# Arduino-MEGA.net
KiCad netlist of a schematic drawn in EAGLE
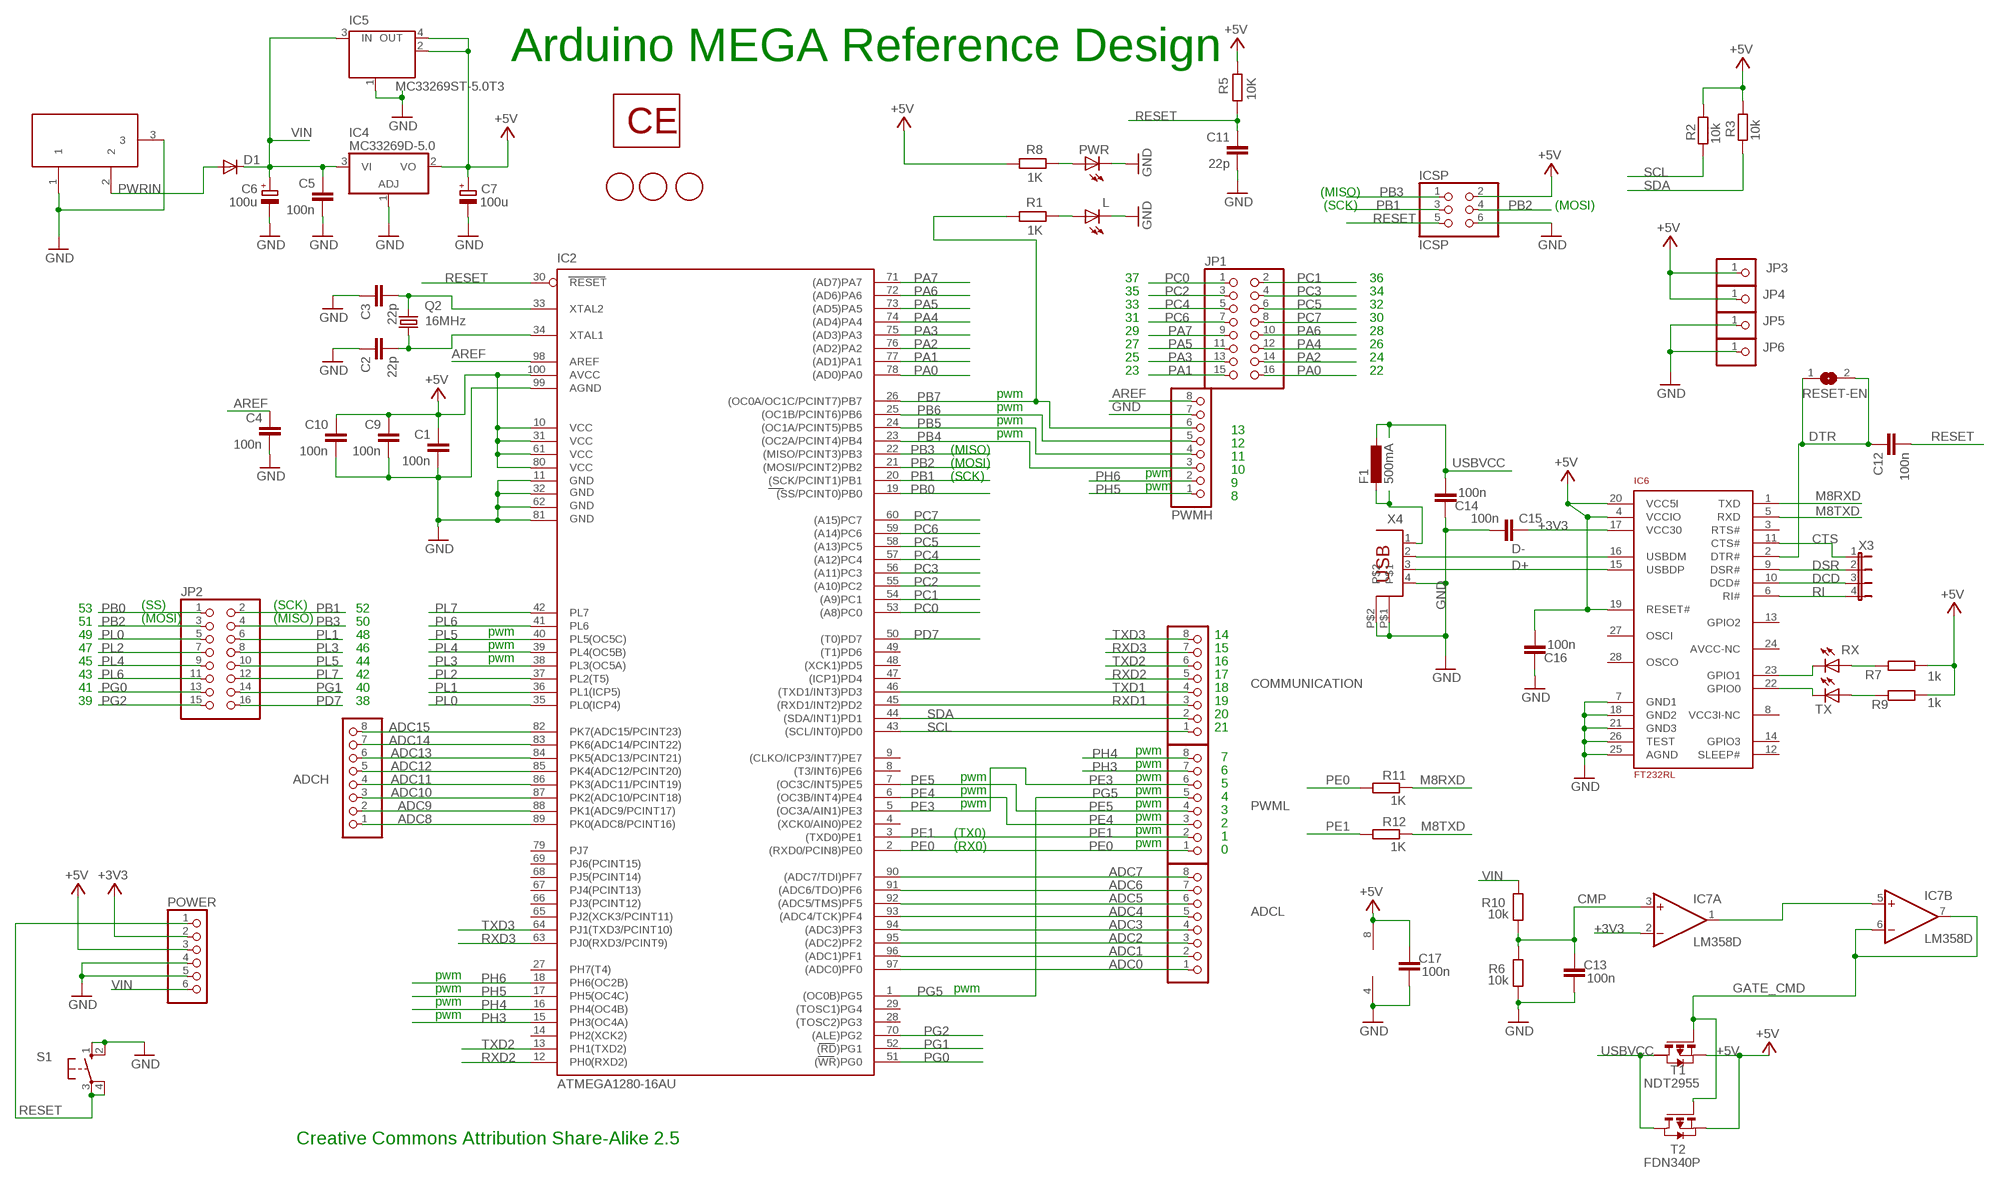
[diagram p0: schematic, sheet 1]

(export (version "E")
  (design (tool "Eeschema 10.0.6"))
  (components
    (comp (ref "ADCH")
      (value "PINHD-1X8")
      (footprint "eagle-import:1X08")
      (libsource (lib "eagle-import") (part "PINHD-1X8"))
    )
    (comp (ref "ADCL")
      (value "PINHD-1X8")
      (footprint "eagle-import:1X08")
      (libsource (lib "eagle-import") (part "PINHD-1X8"))
    )
    (comp (ref "C1")
      (value "100n")
      (footprint "eagle-import:C0805RND")
      (libsource (lib "eagle-import") (part "C-EU"))
    )
    (comp (ref "C2")
      (value "22p")
      (footprint "eagle-import:C0805RND")
      (libsource (lib "eagle-import") (part "C-EU"))
    )
    (comp (ref "C3")
      (value "22p")
      (footprint "eagle-import:C0805RND")
      (libsource (lib "eagle-import") (part "C-EU"))
    )
    (comp (ref "C4")
      (value "100n")
      (footprint "eagle-import:C0805RND")
      (libsource (lib "eagle-import") (part "C-EU"))
    )
    (comp (ref "C5")
      (value "100n")
      (footprint "eagle-import:C0805RND")
      (libsource (lib "eagle-import") (part "C-EU"))
    )
    (comp (ref "C6")
      (value "100u")
      (footprint "eagle-import:SMC_D")
      (libsource (lib "eagle-import") (part "CPOL-EUSMCD"))
    )
    (comp (ref "C7")
      (value "100u")
      (footprint "eagle-import:SMC_D")
      (libsource (lib "eagle-import") (part "CPOL-EUSMCD"))
    )
    (comp (ref "C9")
      (value "100n")
      (footprint "eagle-import:C0805RND")
      (libsource (lib "eagle-import") (part "C-EU"))
    )
    (comp (ref "C10")
      (value "100n")
      (footprint "eagle-import:C0805RND")
      (libsource (lib "eagle-import") (part "C-EU"))
    )
    (comp (ref "C11")
      (value "22p")
      (footprint "eagle-import:C0805RND")
      (libsource (lib "eagle-import") (part "C-EU"))
    )
    (comp (ref "C12")
      (value "100n")
      (footprint "eagle-import:C0805RND")
      (libsource (lib "eagle-import") (part "C-EU"))
    )
    (comp (ref "C13")
      (value "100n")
      (footprint "eagle-import:C0805RND")
      (libsource (lib "eagle-import") (part "C-EU"))
    )
    (comp (ref "C14")
      (value "100n")
      (footprint "eagle-import:C0805RND")
      (libsource (lib "eagle-import") (part "C-EU"))
    )
    (comp (ref "C15")
      (value "100n")
      (footprint "eagle-import:C0805RND")
      (libsource (lib "eagle-import") (part "C-EU"))
    )
    (comp (ref "C16")
      (value "100n")
      (footprint "eagle-import:C0805RND")
      (libsource (lib "eagle-import") (part "C-EU"))
    )
    (comp (ref "C17")
      (value "100n")
      (footprint "eagle-import:C0805RND")
      (libsource (lib "eagle-import") (part "C-EU"))
    )
    (comp (ref "COMMUNICATION")
      (value "PINHD-1X8")
      (footprint "eagle-import:1X08")
      (libsource (lib "eagle-import") (part "PINHD-1X8"))
    )
    (comp (ref "D1")
      (value "DIODE-SMB")
      (footprint "eagle-import:SMB")
      (libsource (lib "eagle-import") (part "DIODE-SMB"))
    )
    (comp (ref "F1")
      (value "500mA")
      (footprint "eagle-import:L1812")
      (libsource (lib "eagle-import") (part "L-EUL1812"))
    )
    (comp (ref "IC2")
      (value "ATMEGA1280-16AU")
      (footprint "eagle-import:TQFP100")
      (libsource (lib "eagle-import") (part "ATMEGAAU1280-16"))
    )
    (comp (ref "IC4")
      (value "MC33269D-5.0")
      (footprint "eagle-import:DPACK")
      (libsource (lib "eagle-import") (part "MC33269?D-5.0"))
    )
    (comp (ref "IC5")
      (value "MC33269ST-5.0T3")
      (footprint "eagle-import:SOT223")
      (libsource (lib "eagle-import") (part "MC33269ST-3.3T3"))
    )
    (comp (ref "IC6")
      (value "FT232RL")
      (footprint "eagle-import:SSOP28")
      (libsource (lib "eagle-import") (part "FT232RL"))
    )
    (comp (ref "IC7")
      (value "LM358D")
      (footprint "eagle-import:SO08")
      (libsource (lib "eagle-import") (part "LM358D"))
    )
    (comp (ref "ICSP")
      (value "ICSP")
      (footprint "eagle-import:2X03")
      (libsource (lib "eagle-import") (part "PINHD-2X3"))
    )
    (comp (ref "JP1")
      (value "PINHD-2X8")
      (footprint "eagle-import:2X08")
      (libsource (lib "eagle-import") (part "PINHD-2X8"))
    )
    (comp (ref "JP2")
      (value "PINHD-2X8")
      (footprint "eagle-import:2X08")
      (libsource (lib "eagle-import") (part "PINHD-2X8"))
    )
    (comp (ref "JP3")
      (value "PINHD-1X1")
      (footprint "eagle-import:1X01")
      (libsource (lib "eagle-import") (part "PINHD-1X1"))
    )
    (comp (ref "JP4")
      (value "PINHD-1X1")
      (footprint "eagle-import:1X01")
      (libsource (lib "eagle-import") (part "PINHD-1X1"))
    )
    (comp (ref "JP5")
      (value "PINHD-1X1")
      (footprint "eagle-import:1X01")
      (libsource (lib "eagle-import") (part "PINHD-1X1"))
    )
    (comp (ref "JP6")
      (value "PINHD-1X1")
      (footprint "eagle-import:1X01")
      (libsource (lib "eagle-import") (part "PINHD-1X1"))
    )
    (comp (ref "L")
      (value "LED0805ROUND")
      (footprint "eagle-import:0805RND")
      (libsource (lib "eagle-import") (part "LED0805ROUND"))
    )
    (comp (ref "POWER")
      (value "PINHD-1X6")
      (footprint "eagle-import:1X06")
      (libsource (lib "eagle-import") (part "PINHD-1X6"))
    )
    (comp (ref "PWMH")
      (value "PINHD-1X8")
      (footprint "eagle-import:1X08")
      (libsource (lib "eagle-import") (part "PINHD-1X8"))
    )
    (comp (ref "PWML")
      (value "PINHD-1X8")
      (footprint "eagle-import:1X08")
      (libsource (lib "eagle-import") (part "PINHD-1X8"))
    )
    (comp (ref "PWR")
      (value "LED0805ROUND")
      (footprint "eagle-import:0805RND")
      (libsource (lib "eagle-import") (part "LED0805ROUND"))
    )
    (comp (ref "Q2")
      (value "16MHz")
      (footprint "eagle-import:HC49_S")
      (libsource (lib "eagle-import") (part "CRYTALHC49S"))
    )
    (comp (ref "R1")
      (value "1K")
      (footprint "eagle-import:R0805RND")
      (libsource (lib "eagle-import") (part "rcl_R-EU_"))
    )
    (comp (ref "R2")
      (value "10k")
      (footprint "eagle-import:R0805RND")
      (libsource (lib "eagle-import") (part "rcl_R-EU_"))
    )
    (comp (ref "R3")
      (value "10k")
      (footprint "eagle-import:R0805RND")
      (libsource (lib "eagle-import") (part "rcl_R-EU_"))
    )
    (comp (ref "R5")
      (value "10K")
      (footprint "eagle-import:R0805RND")
      (libsource (lib "eagle-import") (part "rcl_R-EU_"))
    )
    (comp (ref "R6")
      (value "10k")
      (footprint "eagle-import:R0805RND")
      (libsource (lib "eagle-import") (part "rcl_R-EU_"))
    )
    (comp (ref "R7")
      (value "1k")
      (footprint "eagle-import:R0805RND")
      (libsource (lib "eagle-import") (part "rcl_R-EU_"))
    )
    (comp (ref "R8")
      (value "1K")
      (footprint "eagle-import:R0805RND")
      (libsource (lib "eagle-import") (part "rcl_R-EU_"))
    )
    (comp (ref "R9")
      (value "1k")
      (footprint "eagle-import:R0805RND")
      (libsource (lib "eagle-import") (part "rcl_R-EU_"))
    )
    (comp (ref "R10")
      (value "10k")
      (footprint "eagle-import:R0805RND")
      (libsource (lib "eagle-import") (part "rcl_R-EU_"))
    )
    (comp (ref "R11")
      (value "1K")
      (footprint "eagle-import:RCL_0805RND")
      (libsource (lib "eagle-import") (part "R-EU_"))
    )
    (comp (ref "R12")
      (value "1K")
      (footprint "eagle-import:RCL_0805RND")
      (libsource (lib "eagle-import") (part "R-EU_"))
    )
    (comp (ref "RESET-EN")
      (value "SJ")
      (footprint "eagle-import:SJ")
      (libsource (lib "eagle-import") (part "SJ"))
    )
    (comp (ref "RX")
      (value "LED0805ROUND")
      (footprint "eagle-import:0805RND")
      (libsource (lib "eagle-import") (part "LED0805ROUND"))
    )
    (comp (ref "S1")
      (value "10-XX")
      (footprint "eagle-import:B3F-10XX")
      (libsource (lib "eagle-import") (part "10-XX"))
    )
    (comp (ref "T1")
      (value "NDT2955")
      (footprint "eagle-import:SOT223")
      (libsource (lib "eagle-import") (part "PMOSSOT223"))
    )
    (comp (ref "T2")
      (value "FDN340P")
      (footprint "eagle-import:SOT-23")
      (libsource (lib "eagle-import") (part "PMOSSOT23"))
    )
    (comp (ref "TX")
      (value "LED0805ROUND")
      (footprint "eagle-import:0805RND")
      (libsource (lib "eagle-import") (part "LED0805ROUND"))
    )
    (comp (ref "U$1")
      (value "FIDUCIALMOUNT")
      (footprint "eagle-import:FIDUCIA-MOUNT")
      (libsource (lib "eagle-import") (part "FIDUCIALMOUNT"))
    )
    (comp (ref "U$2")
      (value "FIDUCIALMOUNT")
      (footprint "eagle-import:FIDUCIA-MOUNT")
      (libsource (lib "eagle-import") (part "FIDUCIALMOUNT"))
    )
    (comp (ref "U$3")
      (value "FIDUCIALMOUNT")
      (footprint "eagle-import:FIDUCIA-MOUNT")
      (libsource (lib "eagle-import") (part "FIDUCIALMOUNT"))
    )
    (comp (ref "U$4")
      (value "CE")
      (footprint "eagle-import:CE-COPPER")
      (libsource (lib "eagle-import") (part "CE"))
    )
    (comp (ref "X2")
      (value "DC21MMX")
      (footprint "eagle-import:DC-21MM")
      (libsource (lib "eagle-import") (part "DC21MMX"))
    )
    (comp (ref "X3")
      (value "JP4E")
      (footprint "eagle-import:JP4")
      (libsource (lib "eagle-import") (part "JP4E"))
    )
    (comp (ref "X4")
      (value "PN61729")
      (footprint "eagle-import:PN61729")
      (libsource (lib "eagle-import") (part "PN61729"))
    )
  )
  (nets
    (net (code "1") (name "+3V3") (class "Default")
      (node (ref "C15") (pin "2") (pinfunction "2_2") (pintype "passive"))
      (node (ref "IC6") (pin "17") (pinfunction "VCC30_17") (pintype "power_in"))
      (node (ref "IC7") (pin "2") (pinfunction "-IN_2") (pintype "input"))
      (node (ref "POWER") (pin "2") (pinfunction "2_2") (pintype "passive"))
    )
    (net (code "2") (name "+5V") (class "Default")
      (node (ref "C1") (pin "1") (pinfunction "1_1") (pintype "passive"))
      (node (ref "C10") (pin "1") (pinfunction "1_1") (pintype "passive"))
      (node (ref "C16") (pin "1") (pinfunction "1_1") (pintype "passive"))
      (node (ref "C17") (pin "2") (pinfunction "2_2") (pintype "passive"))
      (node (ref "C7") (pin "+") (pinfunction "+_+") (pintype "passive"))
      (node (ref "C9") (pin "1") (pinfunction "1_1") (pintype "passive"))
      (node (ref "IC2") (pin "10") (pinfunction "VCC_10") (pintype "power_in"))
      (node (ref "IC2") (pin "100") (pinfunction "AVCC_100") (pintype "power_in"))
      (node (ref "IC2") (pin "31") (pinfunction "VCC1_31") (pintype "power_in"))
      (node (ref "IC2") (pin "61") (pinfunction "VCC2_61") (pintype "power_in"))
      (node (ref "IC2") (pin "80") (pinfunction "VCC3_80") (pintype "power_in"))
      (node (ref "IC4") (pin "2") (pinfunction "VO_2") (pintype "passive"))
      (node (ref "IC5") (pin "2") (pinfunction "OUT_2") (pintype "passive"))
      (node (ref "IC5") (pin "4") (pinfunction "OUT_4") (pintype "passive"))
      (node (ref "IC6") (pin "19") (pinfunction "RESET#_19") (pintype "input"))
      (node (ref "IC6") (pin "20") (pinfunction "VCC5I_20") (pintype "power_in"))
      (node (ref "IC6") (pin "4") (pinfunction "VCCIO_4") (pintype "power_in"))
      (node (ref "IC7") (pin "8") (pinfunction "V+_8") (pintype "power_in"))
      (node (ref "ICSP") (pin "2") (pinfunction "2_2") (pintype "passive"))
      (node (ref "JP3") (pin "1") (pinfunction "1_1") (pintype "passive"))
      (node (ref "JP4") (pin "1") (pinfunction "1_1") (pintype "passive"))
      (node (ref "POWER") (pin "3") (pinfunction "3_3") (pintype "passive"))
      (node (ref "R2") (pin "1") (pinfunction "1_1") (pintype "passive"))
      (node (ref "R3") (pin "1") (pinfunction "1_1") (pintype "passive"))
      (node (ref "R5") (pin "2") (pinfunction "2_2") (pintype "passive"))
      (node (ref "R7") (pin "2") (pinfunction "2_2") (pintype "passive"))
      (node (ref "R8") (pin "1") (pinfunction "1_1") (pintype "passive"))
      (node (ref "R9") (pin "2") (pinfunction "2_2") (pintype "passive"))
      (node (ref "T1") (pin "3") (pinfunction "S_3") (pintype "passive"))
      (node (ref "T2") (pin "2") (pinfunction "S_2") (pintype "passive"))
    )
    (net (code "3") (name "/ADC0") (class "Default")
      (node (ref "ADCL") (pin "1") (pinfunction "1_1") (pintype "passive"))
      (node (ref "IC2") (pin "97") (pinfunction "(ADC0)PF0_97") (pintype "bidirectional"))
    )
    (net (code "4") (name "/ADC1") (class "Default")
      (node (ref "ADCL") (pin "2") (pinfunction "2_2") (pintype "passive"))
      (node (ref "IC2") (pin "96") (pinfunction "(ADC1)PF1_96") (pintype "bidirectional"))
    )
    (net (code "5") (name "/ADC2") (class "Default")
      (node (ref "ADCL") (pin "3") (pinfunction "3_3") (pintype "passive"))
      (node (ref "IC2") (pin "95") (pinfunction "(ADC2)PF2_95") (pintype "bidirectional"))
    )
    (net (code "6") (name "/ADC3") (class "Default")
      (node (ref "ADCL") (pin "4") (pinfunction "4_4") (pintype "passive"))
      (node (ref "IC2") (pin "94") (pinfunction "(ADC3)PF3_94") (pintype "bidirectional"))
    )
    (net (code "7") (name "/ADC4") (class "Default")
      (node (ref "ADCL") (pin "5") (pinfunction "5_5") (pintype "passive"))
      (node (ref "IC2") (pin "93") (pinfunction "(ADC4/TCK)PF4_93") (pintype "bidirectional"))
    )
    (net (code "8") (name "/ADC5") (class "Default")
      (node (ref "ADCL") (pin "6") (pinfunction "6_6") (pintype "passive"))
      (node (ref "IC2") (pin "92") (pinfunction "(ADC5/TMS)PF5_92") (pintype "bidirectional"))
    )
    (net (code "9") (name "/ADC6") (class "Default")
      (node (ref "ADCL") (pin "7") (pinfunction "7_7") (pintype "passive"))
      (node (ref "IC2") (pin "91") (pinfunction "(ADC6/TDO)PF6_91") (pintype "bidirectional"))
    )
    (net (code "10") (name "/ADC7") (class "Default")
      (node (ref "ADCL") (pin "8") (pinfunction "8_8") (pintype "passive"))
      (node (ref "IC2") (pin "90") (pinfunction "(ADC7/TDI)PF7_90") (pintype "bidirectional"))
    )
    (net (code "11") (name "/ADC8") (class "Default")
      (node (ref "ADCH") (pin "1") (pinfunction "1_1") (pintype "passive"))
      (node (ref "IC2") (pin "89") (pinfunction "PK0(ADC8/PCINT16)_89") (pintype "bidirectional"))
    )
    (net (code "12") (name "/ADC9") (class "Default")
      (node (ref "ADCH") (pin "2") (pinfunction "2_2") (pintype "passive"))
      (node (ref "IC2") (pin "88") (pinfunction "PK1(ADC9/PCINT17)_88") (pintype "bidirectional"))
    )
    (net (code "13") (name "/ADC10") (class "Default")
      (node (ref "ADCH") (pin "3") (pinfunction "3_3") (pintype "passive"))
      (node (ref "IC2") (pin "87") (pinfunction "PK2(ADC10/PCINT18)_87") (pintype "bidirectional"))
    )
    (net (code "14") (name "/ADC11") (class "Default")
      (node (ref "ADCH") (pin "4") (pinfunction "4_4") (pintype "passive"))
      (node (ref "IC2") (pin "86") (pinfunction "PK3(ADC11/PCINT19)_86") (pintype "bidirectional"))
    )
    (net (code "15") (name "/ADC12") (class "Default")
      (node (ref "ADCH") (pin "5") (pinfunction "5_5") (pintype "passive"))
      (node (ref "IC2") (pin "85") (pinfunction "PK4(ADC12/PCINT20)_85") (pintype "bidirectional"))
    )
    (net (code "16") (name "/ADC13") (class "Default")
      (node (ref "ADCH") (pin "6") (pinfunction "6_6") (pintype "passive"))
      (node (ref "IC2") (pin "84") (pinfunction "PK5(ADC13/PCINT21)_84") (pintype "bidirectional"))
    )
    (net (code "17") (name "/ADC14") (class "Default")
      (node (ref "ADCH") (pin "7") (pinfunction "7_7") (pintype "passive"))
      (node (ref "IC2") (pin "83") (pinfunction "PK6(ADC14/PCINT22)_83") (pintype "bidirectional"))
    )
    (net (code "18") (name "/ADC15") (class "Default")
      (node (ref "ADCH") (pin "8") (pinfunction "8_8") (pintype "passive"))
      (node (ref "IC2") (pin "82") (pinfunction "PK7(ADC15/PCINT23)_82") (pintype "bidirectional"))
    )
    (net (code "19") (name "/AREF") (class "Default")
      (node (ref "C4") (pin "1") (pinfunction "1_1") (pintype "passive"))
      (node (ref "IC2") (pin "98") (pinfunction "AREF_98") (pintype "bidirectional"))
      (node (ref "PWMH") (pin "8") (pinfunction "8_8") (pintype "passive"))
    )
    (net (code "20") (name "/CMP") (class "Default")
      (node (ref "C13") (pin "2") (pinfunction "2_2") (pintype "passive"))
      (node (ref "IC7") (pin "3") (pinfunction "+IN_3") (pintype "input"))
      (node (ref "R10") (pin "1") (pinfunction "1_1") (pintype "passive"))
      (node (ref "R6") (pin "2") (pinfunction "2_2") (pintype "passive"))
    )
    (net (code "21") (name "/CTS") (class "Default")
      (node (ref "IC6") (pin "11") (pinfunction "CTS#_11") (pintype "input"))
      (node (ref "X3") (pin "1") (pinfunction "1_1") (pintype "passive"))
    )
    (net (code "22") (name "/D+") (class "Default")
      (node (ref "IC6") (pin "15") (pinfunction "USBDP_15") (pintype "bidirectional"))
      (node (ref "X4") (pin "3") (pinfunction "3_3") (pintype "bidirectional"))
    )
    (net (code "23") (name "/D-") (class "Default")
      (node (ref "IC6") (pin "16") (pinfunction "USBDM_16") (pintype "bidirectional"))
      (node (ref "X4") (pin "2") (pinfunction "2_2") (pintype "bidirectional"))
    )
    (net (code "24") (name "/DCD") (class "Default")
      (node (ref "IC6") (pin "10") (pinfunction "DCD#_10") (pintype "input"))
      (node (ref "X3") (pin "3") (pinfunction "3_3") (pintype "passive"))
    )
    (net (code "25") (name "/DSR") (class "Default")
      (node (ref "IC6") (pin "9") (pinfunction "DSR#_9") (pintype "input"))
      (node (ref "X3") (pin "2") (pinfunction "2_2") (pintype "passive"))
    )
    (net (code "26") (name "/DTR") (class "Default")
      (node (ref "C12") (pin "1") (pinfunction "1_1") (pintype "passive"))
      (node (ref "IC6") (pin "2") (pinfunction "DTR#_2") (pintype "output"))
      (node (ref "RESET-EN") (pin "1") (pinfunction "1_1") (pintype "passive"))
      (node (ref "RESET-EN") (pin "2") (pinfunction "2_2") (pintype "passive"))
    )
    (net (code "27") (name "/GATE_CMD") (class "Default")
      (node (ref "IC7") (pin "6") (pinfunction "-IN_6") (pintype "input"))
      (node (ref "IC7") (pin "7") (pinfunction "OUT_7") (pintype "output"))
      (node (ref "T1") (pin "1") (pinfunction "G_1") (pintype "passive"))
      (node (ref "T2") (pin "3") (pinfunction "G_3") (pintype "passive"))
    )
    (net (code "28") (name "/M8RXD") (class "Default")
      (node (ref "IC6") (pin "1") (pinfunction "TXD_1") (pintype "output"))
      (node (ref "R11") (pin "P$1") (pinfunction "1_P$1") (pintype "passive"))
    )
    (net (code "29") (name "/M8TXD") (class "Default")
      (node (ref "IC6") (pin "5") (pinfunction "RXD_5") (pintype "input"))
      (node (ref "R12") (pin "P$1") (pinfunction "1_P$1") (pintype "passive"))
    )
    (net (code "30") (name "/PA0") (class "Default")
      (node (ref "IC2") (pin "78") (pinfunction "(AD0)PA0_78") (pintype "bidirectional"))
      (node (ref "JP1") (pin "16") (pinfunction "16_16") (pintype "passive"))
    )
    (net (code "31") (name "/PA1") (class "Default")
      (node (ref "IC2") (pin "77") (pinfunction "(AD1)PA1_77") (pintype "bidirectional"))
      (node (ref "JP1") (pin "15") (pinfunction "15_15") (pintype "passive"))
    )
    (net (code "32") (name "/PA2") (class "Default")
      (node (ref "IC2") (pin "76") (pinfunction "(AD2)PA2_76") (pintype "bidirectional"))
      (node (ref "JP1") (pin "14") (pinfunction "14_14") (pintype "passive"))
    )
    (net (code "33") (name "/PA3") (class "Default")
      (node (ref "IC2") (pin "75") (pinfunction "(AD3)PA3_75") (pintype "bidirectional"))
      (node (ref "JP1") (pin "13") (pinfunction "13_13") (pintype "passive"))
    )
    (net (code "34") (name "/PA4") (class "Default")
      (node (ref "IC2") (pin "74") (pinfunction "(AD4)PA4_74") (pintype "bidirectional"))
      (node (ref "JP1") (pin "12") (pinfunction "12_12") (pintype "passive"))
    )
    (net (code "35") (name "/PA5") (class "Default")
      (node (ref "IC2") (pin "73") (pinfunction "(AD5)PA5_73") (pintype "bidirectional"))
      (node (ref "JP1") (pin "11") (pinfunction "11_11") (pintype "passive"))
    )
    (net (code "36") (name "/PA6") (class "Default")
      (node (ref "IC2") (pin "72") (pinfunction "(AD6)PA6_72") (pintype "bidirectional"))
      (node (ref "JP1") (pin "10") (pinfunction "10_10") (pintype "passive"))
    )
    (net (code "37") (name "/PA7") (class "Default")
      (node (ref "IC2") (pin "71") (pinfunction "(AD7)PA7_71") (pintype "bidirectional"))
      (node (ref "JP1") (pin "9") (pinfunction "9_9") (pintype "passive"))
    )
    (net (code "38") (name "/PB0") (class "Default")
      (node (ref "IC2") (pin "19") (pinfunction "(SS/PCINT0)PB0_19") (pintype "bidirectional"))
      (node (ref "JP2") (pin "1") (pinfunction "1_1") (pintype "passive"))
    )
    (net (code "39") (name "/PB1") (class "Default")
      (node (ref "IC2") (pin "20") (pinfunction "(SCK/PCINT1)PB1_20") (pintype "bidirectional"))
      (node (ref "ICSP") (pin "3") (pinfunction "3_3") (pintype "passive"))
      (node (ref "JP2") (pin "2") (pinfunction "2_2") (pintype "passive"))
    )
    (net (code "40") (name "/PB2") (class "Default")
      (node (ref "IC2") (pin "21") (pinfunction "(MOSI/PCINT2)PB2_21") (pintype "bidirectional"))
      (node (ref "ICSP") (pin "4") (pinfunction "4_4") (pintype "passive"))
      (node (ref "JP2") (pin "3") (pinfunction "3_3") (pintype "passive"))
    )
    (net (code "41") (name "/PB3") (class "Default")
      (node (ref "IC2") (pin "22") (pinfunction "(MISO/PCINT3)PB3_22") (pintype "bidirectional"))
      (node (ref "ICSP") (pin "1") (pinfunction "1_1") (pintype "passive"))
      (node (ref "JP2") (pin "4") (pinfunction "4_4") (pintype "passive"))
    )
    (net (code "42") (name "/PB4") (class "Default")
      (node (ref "IC2") (pin "23") (pinfunction "(OC2A/PCINT4)PB4_23") (pintype "bidirectional"))
      (node (ref "PWMH") (pin "3") (pinfunction "3_3") (pintype "passive"))
    )
    (net (code "43") (name "/PB5") (class "Default")
      (node (ref "IC2") (pin "24") (pinfunction "(OC1A/PCINT5)PB5_24") (pintype "bidirectional"))
      (node (ref "PWMH") (pin "4") (pinfunction "4_4") (pintype "passive"))
    )
    (net (code "44") (name "/PB6") (class "Default")
      (node (ref "IC2") (pin "25") (pinfunction "(OC1B/PCINT6)PB6_25") (pintype "bidirectional"))
      (node (ref "PWMH") (pin "5") (pinfunction "5_5") (pintype "passive"))
    )
    (net (code "45") (name "/PB7") (class "Default")
      (node (ref "IC2") (pin "26") (pinfunction "(OC0A/OC1C/PCINT7)PB7_26") (pintype "bidirectional"))
      (node (ref "PWMH") (pin "6") (pinfunction "6_6") (pintype "passive"))
      (node (ref "R1") (pin "1") (pinfunction "1_1") (pintype "passive"))
    )
    (net (code "46") (name "/PC0") (class "Default")
      (node (ref "IC2") (pin "53") (pinfunction "(A8)PC0_53") (pintype "bidirectional"))
      (node (ref "JP1") (pin "1") (pinfunction "1_1") (pintype "passive"))
    )
    (net (code "47") (name "/PC1") (class "Default")
      (node (ref "IC2") (pin "54") (pinfunction "(A9)PC1_54") (pintype "bidirectional"))
      (node (ref "JP1") (pin "2") (pinfunction "2_2") (pintype "passive"))
    )
    (net (code "48") (name "/PC2") (class "Default")
      (node (ref "IC2") (pin "55") (pinfunction "(A10)PC2_55") (pintype "bidirectional"))
      (node (ref "JP1") (pin "3") (pinfunction "3_3") (pintype "passive"))
    )
    (net (code "49") (name "/PC3") (class "Default")
      (node (ref "IC2") (pin "56") (pinfunction "(A11)PC3_56") (pintype "bidirectional"))
      (node (ref "JP1") (pin "4") (pinfunction "4_4") (pintype "passive"))
    )
    (net (code "50") (name "/PC4") (class "Default")
      (node (ref "IC2") (pin "57") (pinfunction "(A12)PC4_57") (pintype "bidirectional"))
      (node (ref "JP1") (pin "5") (pinfunction "5_5") (pintype "passive"))
    )
    (net (code "51") (name "/PC5") (class "Default")
      (node (ref "IC2") (pin "58") (pinfunction "(A13)PC5_58") (pintype "bidirectional"))
      (node (ref "JP1") (pin "6") (pinfunction "6_6") (pintype "passive"))
    )
    (net (code "52") (name "/PC6") (class "Default")
      (node (ref "IC2") (pin "59") (pinfunction "(A14)PC6_59") (pintype "bidirectional"))
      (node (ref "JP1") (pin "7") (pinfunction "7_7") (pintype "passive"))
    )
    (net (code "53") (name "/PC7") (class "Default")
      (node (ref "IC2") (pin "60") (pinfunction "(A15)PC7_60") (pintype "bidirectional"))
      (node (ref "JP1") (pin "8") (pinfunction "8_8") (pintype "passive"))
    )
    (net (code "54") (name "/PD7") (class "Default")
      (node (ref "IC2") (pin "50") (pinfunction "(T0)PD7_50") (pintype "bidirectional"))
      (node (ref "JP2") (pin "16") (pinfunction "16_16") (pintype "passive"))
    )
    (net (code "55") (name "/PE0") (class "Default")
      (node (ref "IC2") (pin "2") (pinfunction "(RXD0/PCIN8)PE0_2") (pintype "bidirectional"))
      (node (ref "PWML") (pin "1") (pinfunction "1_1") (pintype "passive"))
      (node (ref "R11") (pin "P$2") (pinfunction "2_P$2") (pintype "passive"))
    )
    (net (code "56") (name "/PE1") (class "Default")
      (node (ref "IC2") (pin "3") (pinfunction "(TXD0)PE1_3") (pintype "bidirectional"))
      (node (ref "PWML") (pin "2") (pinfunction "2_2") (pintype "passive"))
      (node (ref "R12") (pin "P$2") (pinfunction "2_P$2") (pintype "passive"))
    )
    (net (code "57") (name "/PE3") (class "Default")
      (node (ref "IC2") (pin "5") (pinfunction "(OC3A/AIN1)PE3_5") (pintype "bidirectional"))
      (node (ref "PWML") (pin "6") (pinfunction "6_6") (pintype "passive"))
    )
    (net (code "58") (name "/PE4") (class "Default")
      (node (ref "IC2") (pin "6") (pinfunction "(OC3B/INT4)PE4_6") (pintype "bidirectional"))
      (node (ref "PWML") (pin "3") (pinfunction "3_3") (pintype "passive"))
    )
    (net (code "59") (name "/PE5") (class "Default")
      (node (ref "IC2") (pin "7") (pinfunction "(OC3C/INT5)PE5_7") (pintype "bidirectional"))
      (node (ref "PWML") (pin "4") (pinfunction "4_4") (pintype "passive"))
    )
    (net (code "60") (name "/PG0") (class "Default")
      (node (ref "IC2") (pin "51") (pinfunction "(WR)PG0_51") (pintype "bidirectional"))
      (node (ref "JP2") (pin "13") (pinfunction "13_13") (pintype "passive"))
    )
    (net (code "61") (name "/PG1") (class "Default")
      (node (ref "IC2") (pin "52") (pinfunction "(RD)PG1_52") (pintype "bidirectional"))
      (node (ref "JP2") (pin "14") (pinfunction "14_14") (pintype "passive"))
    )
    (net (code "62") (name "/PG2") (class "Default")
      (node (ref "IC2") (pin "70") (pinfunction "(ALE)PG2_70") (pintype "bidirectional"))
      (node (ref "JP2") (pin "15") (pinfunction "15_15") (pintype "passive"))
    )
    (net (code "63") (name "/PG5") (class "Default")
      (node (ref "IC2") (pin "1") (pinfunction "(OC0B)PG5_1") (pintype "bidirectional"))
      (node (ref "PWML") (pin "5") (pinfunction "5_5") (pintype "passive"))
    )
    (net (code "64") (name "/PH3") (class "Default")
      (node (ref "IC2") (pin "15") (pinfunction "PH3(OC4A)_15") (pintype "bidirectional"))
      (node (ref "PWML") (pin "7") (pinfunction "7_7") (pintype "passive"))
    )
    (net (code "65") (name "/PH4") (class "Default")
      (node (ref "IC2") (pin "16") (pinfunction "PH4(OC4B)_16") (pintype "bidirectional"))
      (node (ref "PWML") (pin "8") (pinfunction "8_8") (pintype "passive"))
    )
    (net (code "66") (name "/PH5") (class "Default")
      (node (ref "IC2") (pin "17") (pinfunction "PH5(OC4C)_17") (pintype "bidirectional"))
      (node (ref "PWMH") (pin "1") (pinfunction "1_1") (pintype "passive"))
    )
    (net (code "67") (name "/PH6") (class "Default")
      (node (ref "IC2") (pin "18") (pinfunction "PH6(OC2B)_18") (pintype "bidirectional"))
      (node (ref "PWMH") (pin "2") (pinfunction "2_2") (pintype "passive"))
    )
    (net (code "68") (name "/PL0") (class "Default")
      (node (ref "IC2") (pin "35") (pinfunction "PL0(ICP4)_35") (pintype "bidirectional"))
      (node (ref "JP2") (pin "5") (pinfunction "5_5") (pintype "passive"))
    )
    (net (code "69") (name "/PL1") (class "Default")
      (node (ref "IC2") (pin "36") (pinfunction "PL1(ICP5)_36") (pintype "bidirectional"))
      (node (ref "JP2") (pin "6") (pinfunction "6_6") (pintype "passive"))
    )
    (net (code "70") (name "/PL2") (class "Default")
      (node (ref "IC2") (pin "37") (pinfunction "PL2(T5)_37") (pintype "bidirectional"))
      (node (ref "JP2") (pin "7") (pinfunction "7_7") (pintype "passive"))
    )
    (net (code "71") (name "/PL3") (class "Default")
      (node (ref "IC2") (pin "38") (pinfunction "PL3(OC5A)_38") (pintype "bidirectional"))
      (node (ref "JP2") (pin "8") (pinfunction "8_8") (pintype "passive"))
    )
    (net (code "72") (name "/PL4") (class "Default")
      (node (ref "IC2") (pin "39") (pinfunction "PL4(OC5B)_39") (pintype "bidirectional"))
      (node (ref "JP2") (pin "9") (pinfunction "9_9") (pintype "passive"))
    )
    (net (code "73") (name "/PL5") (class "Default")
      (node (ref "IC2") (pin "40") (pinfunction "PL5(OC5C)_40") (pintype "bidirectional"))
      (node (ref "JP2") (pin "10") (pinfunction "10_10") (pintype "passive"))
    )
    (net (code "74") (name "/PL6") (class "Default")
      (node (ref "IC2") (pin "41") (pinfunction "PL6_41") (pintype "bidirectional"))
      (node (ref "JP2") (pin "11") (pinfunction "11_11") (pintype "passive"))
    )
    (net (code "75") (name "/PL7") (class "Default")
      (node (ref "IC2") (pin "42") (pinfunction "PL7_42") (pintype "bidirectional"))
      (node (ref "JP2") (pin "12") (pinfunction "12_12") (pintype "passive"))
    )
    (net (code "76") (name "/PWRIN") (class "Default")
      (node (ref "D1") (pin "A") (pinfunction "A_A") (pintype "passive"))
      (node (ref "X2") (pin "2") (pinfunction "2_2") (pintype "power_in"))
    )
    (net (code "77") (name "/RESET") (class "Default")
      (node (ref "C11") (pin "1") (pinfunction "1_1") (pintype "passive"))
      (node (ref "C12") (pin "2") (pinfunction "2_2") (pintype "passive"))
      (node (ref "IC2") (pin "30") (pinfunction "RESET_30") (pintype "input"))
      (node (ref "ICSP") (pin "5") (pinfunction "5_5") (pintype "passive"))
      (node (ref "POWER") (pin "1") (pinfunction "1_1") (pintype "passive"))
      (node (ref "R5") (pin "1") (pinfunction "1_1") (pintype "passive"))
      (node (ref "S1") (pin "3") (pinfunction "P_3") (pintype "passive"))
      (node (ref "S1") (pin "4") (pinfunction "P1_4") (pintype "passive"))
    )
    (net (code "78") (name "/RI") (class "Default")
      (node (ref "IC6") (pin "6") (pinfunction "RI#_6") (pintype "input"))
      (node (ref "X3") (pin "4") (pinfunction "4_4") (pintype "passive"))
    )
    (net (code "79") (name "/RXD1") (class "Default")
      (node (ref "COMMUNICATION") (pin "3") (pinfunction "3_3") (pintype "passive"))
      (node (ref "IC2") (pin "45") (pinfunction "(RXD1/INT2)PD2_45") (pintype "bidirectional"))
    )
    (net (code "80") (name "/RXD2") (class "Default")
      (node (ref "COMMUNICATION") (pin "5") (pinfunction "5_5") (pintype "passive"))
      (node (ref "IC2") (pin "12") (pinfunction "PH0(RXD2)_12") (pintype "bidirectional"))
    )
    (net (code "81") (name "/RXD3") (class "Default")
      (node (ref "COMMUNICATION") (pin "7") (pinfunction "7_7") (pintype "passive"))
      (node (ref "IC2") (pin "63") (pinfunction "PJ0(RXD3/PCINT9)_63") (pintype "bidirectional"))
    )
    (net (code "82") (name "/SCL") (class "Default")
      (node (ref "COMMUNICATION") (pin "1") (pinfunction "1_1") (pintype "passive"))
      (node (ref "IC2") (pin "43") (pinfunction "(SCL/INT0)PD0_43") (pintype "bidirectional"))
      (node (ref "R2") (pin "2") (pinfunction "2_2") (pintype "passive"))
    )
    (net (code "83") (name "/SDA") (class "Default")
      (node (ref "COMMUNICATION") (pin "2") (pinfunction "2_2") (pintype "passive"))
      (node (ref "IC2") (pin "44") (pinfunction "(SDA/INT1)PD1_44") (pintype "bidirectional"))
      (node (ref "R3") (pin "2") (pinfunction "2_2") (pintype "passive"))
    )
    (net (code "84") (name "/TXD1") (class "Default")
      (node (ref "COMMUNICATION") (pin "4") (pinfunction "4_4") (pintype "passive"))
      (node (ref "IC2") (pin "46") (pinfunction "(TXD1/INT3)PD3_46") (pintype "bidirectional"))
    )
    (net (code "85") (name "/TXD2") (class "Default")
      (node (ref "COMMUNICATION") (pin "6") (pinfunction "6_6") (pintype "passive"))
      (node (ref "IC2") (pin "13") (pinfunction "PH1(TXD2)_13") (pintype "bidirectional"))
    )
    (net (code "86") (name "/TXD3") (class "Default")
      (node (ref "COMMUNICATION") (pin "8") (pinfunction "8_8") (pintype "passive"))
      (node (ref "IC2") (pin "64") (pinfunction "PJ1(TXD3/PCINT10)_64") (pintype "bidirectional"))
    )
    (net (code "87") (name "/USBVCC") (class "Default")
      (node (ref "C14") (pin "1") (pinfunction "1_1") (pintype "passive"))
      (node (ref "F1") (pin "1") (pinfunction "1_1") (pintype "passive"))
      (node (ref "T1") (pin "2") (pinfunction "D_2") (pintype "passive"))
      (node (ref "T2") (pin "1") (pinfunction "D_1") (pintype "passive"))
    )
    (net (code "88") (name "/VIN") (class "Default")
      (node (ref "C5") (pin "1") (pinfunction "1_1") (pintype "passive"))
      (node (ref "C6") (pin "+") (pinfunction "+_+") (pintype "passive"))
      (node (ref "D1") (pin "C") (pinfunction "C_C") (pintype "passive"))
      (node (ref "IC4") (pin "3") (pinfunction "VI_3") (pintype "input"))
      (node (ref "IC5") (pin "3") (pinfunction "IN_3") (pintype "input"))
      (node (ref "POWER") (pin "6") (pinfunction "6_6") (pintype "passive"))
      (node (ref "R10") (pin "2") (pinfunction "2_2") (pintype "passive"))
    )
    (net (code "89") (name "GND") (class "Default")
      (node (ref "C1") (pin "2") (pinfunction "2_2") (pintype "passive"))
      (node (ref "C10") (pin "2") (pinfunction "2_2") (pintype "passive"))
      (node (ref "C11") (pin "2") (pinfunction "2_2") (pintype "passive"))
      (node (ref "C13") (pin "1") (pinfunction "1_1") (pintype "passive"))
      (node (ref "C14") (pin "2") (pinfunction "2_2") (pintype "passive"))
      (node (ref "C15") (pin "1") (pinfunction "1_1") (pintype "passive"))
      (node (ref "C16") (pin "2") (pinfunction "2_2") (pintype "passive"))
      (node (ref "C17") (pin "1") (pinfunction "1_1") (pintype "passive"))
      (node (ref "C2") (pin "1") (pinfunction "1_1") (pintype "passive"))
      (node (ref "C3") (pin "1") (pinfunction "1_1") (pintype "passive"))
      (node (ref "C4") (pin "2") (pinfunction "2_2") (pintype "passive"))
      (node (ref "C5") (pin "2") (pinfunction "2_2") (pintype "passive"))
      (node (ref "C6") (pin "-") (pinfunction "-_-") (pintype "passive"))
      (node (ref "C7") (pin "-") (pinfunction "-_-") (pintype "passive"))
      (node (ref "C9") (pin "2") (pinfunction "2_2") (pintype "passive"))
      (node (ref "IC2") (pin "11") (pinfunction "GND_11") (pintype "power_in"))
      (node (ref "IC2") (pin "32") (pinfunction "GND1_32") (pintype "power_in"))
      (node (ref "IC2") (pin "62") (pinfunction "GND2_62") (pintype "power_in"))
      (node (ref "IC2") (pin "81") (pinfunction "GND3_81") (pintype "power_in"))
      (node (ref "IC2") (pin "99") (pinfunction "AGND_99") (pintype "power_in"))
      (node (ref "IC4") (pin "1") (pinfunction "ADJ_1") (pintype "input"))
      (node (ref "IC5") (pin "1") (pinfunction "GND/ADJ_1") (pintype "input"))
      (node (ref "IC6") (pin "18") (pinfunction "GND2_18") (pintype "power_in"))
      (node (ref "IC6") (pin "21") (pinfunction "GND3_21") (pintype "power_in"))
      (node (ref "IC6") (pin "25") (pinfunction "AGND_25") (pintype "power_in"))
      (node (ref "IC6") (pin "26") (pinfunction "TEST_26") (pintype "input"))
      (node (ref "IC6") (pin "7") (pinfunction "GND1_7") (pintype "power_in"))
      (node (ref "IC7") (pin "4") (pinfunction "V-_4") (pintype "power_in"))
      (node (ref "ICSP") (pin "6") (pinfunction "6_6") (pintype "passive"))
      (node (ref "JP5") (pin "1") (pinfunction "1_1") (pintype "passive"))
      (node (ref "JP6") (pin "1") (pinfunction "1_1") (pintype "passive"))
      (node (ref "L") (pin "P$2") (pinfunction "C_P$2") (pintype "passive"))
      (node (ref "POWER") (pin "4") (pinfunction "4_4") (pintype "passive"))
      (node (ref "POWER") (pin "5") (pinfunction "5_5") (pintype "passive"))
      (node (ref "PWMH") (pin "7") (pinfunction "7_7") (pintype "passive"))
      (node (ref "PWR") (pin "P$2") (pinfunction "C_P$2") (pintype "passive"))
      (node (ref "R6") (pin "1") (pinfunction "1_1") (pintype "passive"))
      (node (ref "S1") (pin "1") (pinfunction "S_1") (pintype "passive"))
      (node (ref "S1") (pin "2") (pinfunction "S1_2") (pintype "passive"))
      (node (ref "X2") (pin "1") (pinfunction "1_1") (pintype "power_in"))
      (node (ref "X2") (pin "3") (pinfunction "3_3") (pintype "power_in"))
      (node (ref "X4") (pin "4") (pinfunction "4_4") (pintype "bidirectional"))
      (node (ref "X4") (pin "P$1") (pinfunction "P$1_P$1") (pintype "bidirectional"))
      (node (ref "X4") (pin "P$2") (pinfunction "P$2_P$2") (pintype "bidirectional"))
    )
    (net (code "90") (name "Net-(F1-Pad2)") (class "Default")
      (node (ref "F1") (pin "2") (pinfunction "2_2") (pintype "passive"))
      (node (ref "X4") (pin "1") (pinfunction "1_1") (pintype "bidirectional"))
    )
    (net (code "91") (name "Net-(IC2-XTAL1)") (class "Default")
      (node (ref "C2") (pin "2") (pinfunction "2_2") (pintype "passive"))
      (node (ref "IC2") (pin "34") (pinfunction "XTAL1_34") (pintype "input"))
      (node (ref "Q2") (pin "1") (pinfunction "1_1") (pintype "passive"))
    )
    (net (code "92") (name "Net-(IC2-XTAL2)") (class "Default")
      (node (ref "C3") (pin "2") (pinfunction "2_2") (pintype "passive"))
      (node (ref "IC2") (pin "33") (pinfunction "XTAL2_33") (pintype "output"))
      (node (ref "Q2") (pin "2") (pinfunction "2_2") (pintype "passive"))
    )
    (net (code "93") (name "Net-(IC6-GPIO0)") (class "Default")
      (node (ref "IC6") (pin "22") (pinfunction "GPIO0_22") (pintype "output"))
      (node (ref "TX") (pin "P$2") (pinfunction "C_P$2") (pintype "passive"))
    )
    (net (code "94") (name "Net-(IC6-GPIO1)") (class "Default")
      (node (ref "IC6") (pin "23") (pinfunction "GPIO1_23") (pintype "output"))
      (node (ref "RX") (pin "P$2") (pinfunction "C_P$2") (pintype "passive"))
    )
    (net (code "95") (name "Net-(IC7A-OUT)") (class "Default")
      (node (ref "IC7") (pin "1") (pinfunction "OUT_1") (pintype "output"))
      (node (ref "IC7") (pin "5") (pinfunction "+IN_5") (pintype "input"))
    )
    (net (code "96") (name "Net-(L-A)") (class "Default")
      (node (ref "L") (pin "P$1") (pinfunction "A_P$1") (pintype "passive"))
      (node (ref "R1") (pin "2") (pinfunction "2_2") (pintype "passive"))
    )
    (net (code "97") (name "Net-(PWR-A)") (class "Default")
      (node (ref "PWR") (pin "P$1") (pinfunction "A_P$1") (pintype "passive"))
      (node (ref "R8") (pin "2") (pinfunction "2_2") (pintype "passive"))
    )
    (net (code "98") (name "Net-(RX-A)") (class "Default")
      (node (ref "R7") (pin "1") (pinfunction "1_1") (pintype "passive"))
      (node (ref "RX") (pin "P$1") (pinfunction "A_P$1") (pintype "passive"))
    )
    (net (code "99") (name "Net-(TX-A)") (class "Default")
      (node (ref "R9") (pin "1") (pinfunction "1_1") (pintype "passive"))
      (node (ref "TX") (pin "P$1") (pinfunction "A_P$1") (pintype "passive"))
    )
    (net (code "100") (name "unconnected-(IC2-(CLKO{slash}ICP3{slash}INT7)PE7-Pad9)") (class "Default")
      (node (ref "IC2") (pin "9") (pinfunction "(CLKO/ICP3/INT7)PE7_9") (pintype "bidirectional"))
    )
    (net (code "101") (name "unconnected-(IC2-(ICP1)PD4-Pad47)") (class "Default")
      (node (ref "IC2") (pin "47") (pinfunction "(ICP1)PD4_47") (pintype "bidirectional"))
    )
    (net (code "102") (name "unconnected-(IC2-(T1)PD6-Pad49)") (class "Default")
      (node (ref "IC2") (pin "49") (pinfunction "(T1)PD6_49") (pintype "bidirectional"))
    )
    (net (code "103") (name "unconnected-(IC2-(T3{slash}INT6)PE6-Pad8)") (class "Default")
      (node (ref "IC2") (pin "8") (pinfunction "(T3/INT6)PE6_8") (pintype "bidirectional"))
    )
    (net (code "104") (name "unconnected-(IC2-(TOSC1)PG4-Pad29)") (class "Default")
      (node (ref "IC2") (pin "29") (pinfunction "(TOSC1)PG4_29") (pintype "bidirectional"))
    )
    (net (code "105") (name "unconnected-(IC2-(TOSC2)PG3-Pad28)") (class "Default")
      (node (ref "IC2") (pin "28") (pinfunction "(TOSC2)PG3_28") (pintype "bidirectional"))
    )
    (net (code "106") (name "unconnected-(IC2-(XCK0{slash}AIN0)PE2-Pad4)") (class "Default")
      (node (ref "IC2") (pin "4") (pinfunction "(XCK0/AIN0)PE2_4") (pintype "bidirectional"))
    )
    (net (code "107") (name "unconnected-(IC2-(XCK1)PD5-Pad48)") (class "Default")
      (node (ref "IC2") (pin "48") (pinfunction "(XCK1)PD5_48") (pintype "bidirectional"))
    )
    (net (code "108") (name "unconnected-(IC2-PH2(XCK2)-Pad14)") (class "Default")
      (node (ref "IC2") (pin "14") (pinfunction "PH2(XCK2)_14") (pintype "bidirectional"))
    )
    (net (code "109") (name "unconnected-(IC2-PH7(T4)-Pad27)") (class "Default")
      (node (ref "IC2") (pin "27") (pinfunction "PH7(T4)_27") (pintype "bidirectional"))
    )
    (net (code "110") (name "unconnected-(IC2-PJ2(XCK3{slash}PCINT11)-Pad65)") (class "Default")
      (node (ref "IC2") (pin "65") (pinfunction "PJ2(XCK3/PCINT11)_65") (pintype "bidirectional"))
    )
    (net (code "111") (name "unconnected-(IC2-PJ3(PCINT12)-Pad66)") (class "Default")
      (node (ref "IC2") (pin "66") (pinfunction "PJ3(PCINT12)_66") (pintype "bidirectional"))
    )
    (net (code "112") (name "unconnected-(IC2-PJ4(PCINT13)-Pad67)") (class "Default")
      (node (ref "IC2") (pin "67") (pinfunction "PJ4(PCINT13)_67") (pintype "bidirectional"))
    )
    (net (code "113") (name "unconnected-(IC2-PJ5(PCINT14)-Pad68)") (class "Default")
      (node (ref "IC2") (pin "68") (pinfunction "PJ5(PCINT14)_68") (pintype "bidirectional"))
    )
    (net (code "114") (name "unconnected-(IC2-PJ6(PCINT15)-Pad69)") (class "Default")
      (node (ref "IC2") (pin "69") (pinfunction "PJ6(PCINT15)_69") (pintype "bidirectional"))
    )
    (net (code "115") (name "unconnected-(IC2-PJ7-Pad79)") (class "Default")
      (node (ref "IC2") (pin "79") (pinfunction "PJ7_79") (pintype "bidirectional"))
    )
    (net (code "116") (name "unconnected-(IC6-AVCC-NC-Pad24)") (class "Default")
      (node (ref "IC6") (pin "24") (pinfunction "AVCC-NC_24") (pintype "no_connect"))
    )
    (net (code "117") (name "unconnected-(IC6-GPIO2-Pad13)") (class "Default")
      (node (ref "IC6") (pin "13") (pinfunction "GPIO2_13") (pintype "output"))
    )
    (net (code "118") (name "unconnected-(IC6-GPIO3-Pad14)") (class "Default")
      (node (ref "IC6") (pin "14") (pinfunction "GPIO3_14") (pintype "input"))
    )
    (net (code "119") (name "unconnected-(IC6-OSCI-Pad27)") (class "Default")
      (node (ref "IC6") (pin "27") (pinfunction "OSCI_27") (pintype "input"))
    )
    (net (code "120") (name "unconnected-(IC6-OSCO-Pad28)") (class "Default")
      (node (ref "IC6") (pin "28") (pinfunction "OSCO_28") (pintype "output"))
    )
    (net (code "121") (name "unconnected-(IC6-RTS#-Pad3)") (class "Default")
      (node (ref "IC6") (pin "3") (pinfunction "RTS#_3") (pintype "output"))
    )
    (net (code "122") (name "unconnected-(IC6-SLEEP#-Pad12)") (class "Default")
      (node (ref "IC6") (pin "12") (pinfunction "SLEEP#_12") (pintype "input"))
    )
    (net (code "123") (name "unconnected-(IC6-VCC3I-NC-Pad8)") (class "Default")
      (node (ref "IC6") (pin "8") (pinfunction "VCC3I-NC_8") (pintype "no_connect"))
    )
    (net (code "124") (name "unconnected-(T1-D2-Pad4)") (class "Default")
      (node (ref "T1") (pin "4") (pinfunction "D2_4") (pintype "passive"))
    )
  )
)
